# Cardy_PCB.net
KiCad netlist of a schematic drawn in EasyEDA Pro
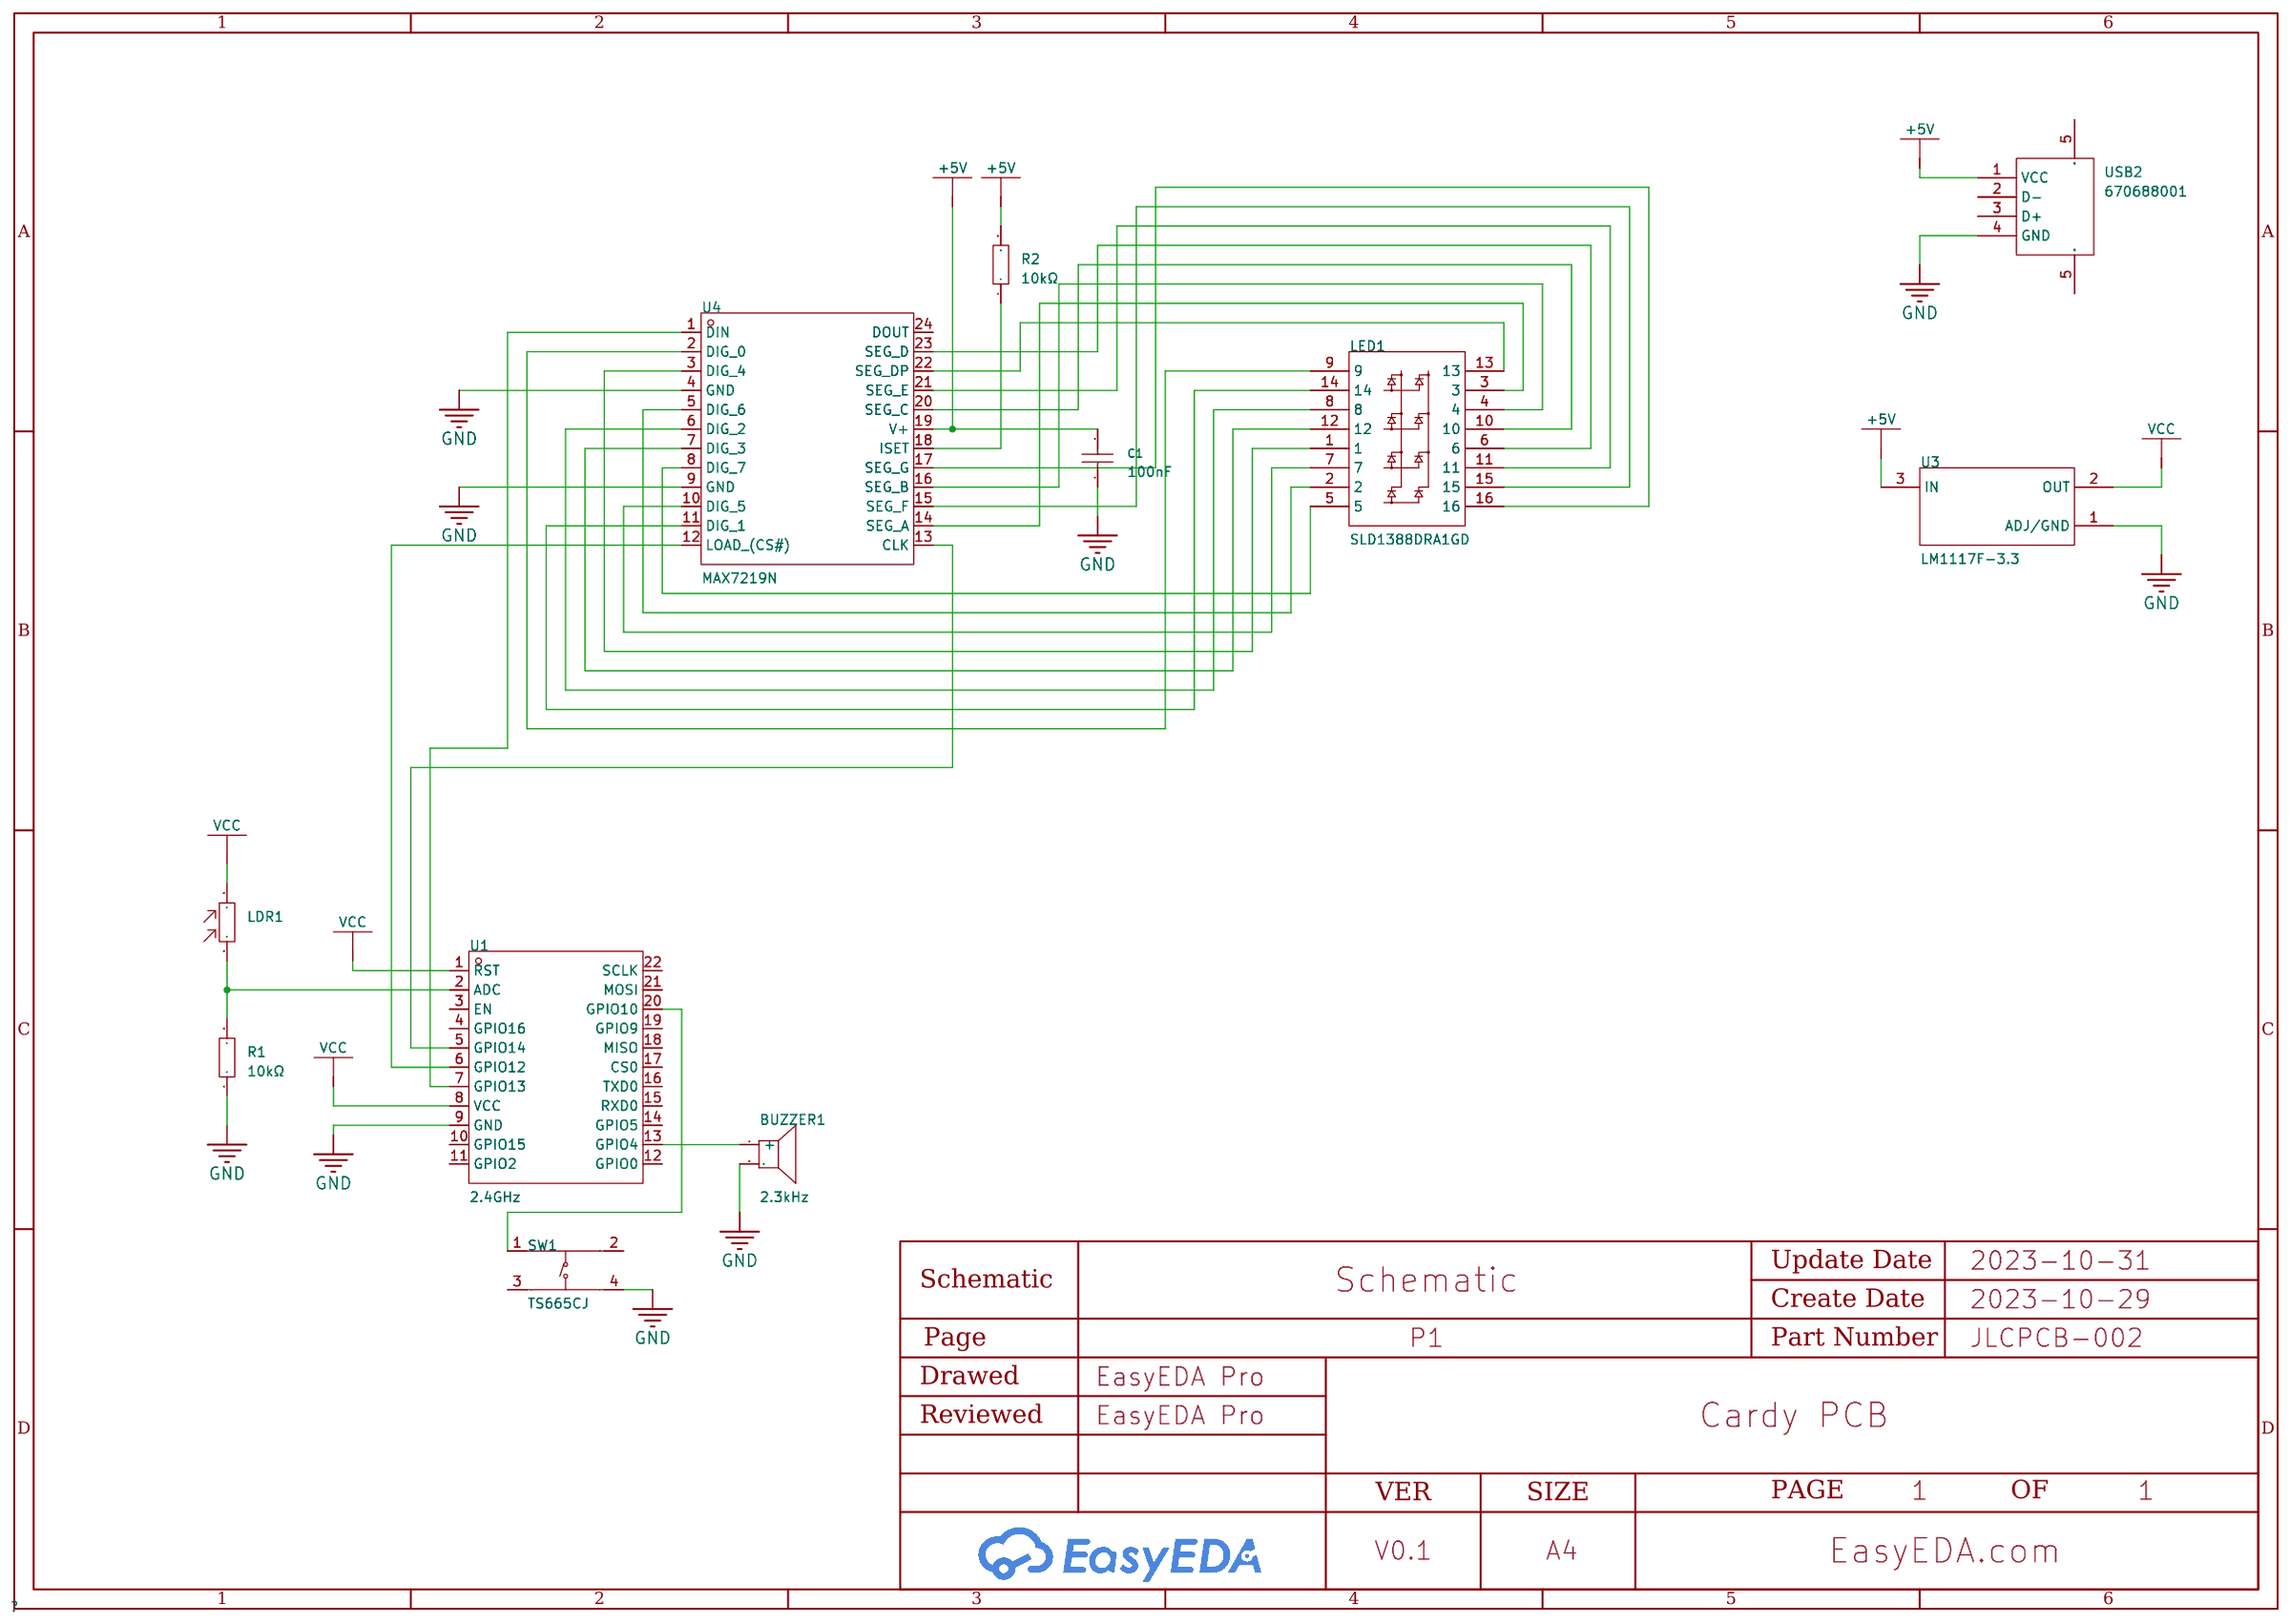
[diagram p0: schematic sheet]

(export (version "E")
  (design (tool "Eeschema 10.0.6"))
  (components
    (comp (ref "BUZZER1")
      (value "2.3kHz")
      (footprint "easyedapro:BUZ-TH_BD12.0-P7.60-D0.6-FD")
      (fields (field (name "Manufacturer Part") "TMB12A05") (field (name "Manufacturer") "华能"))
      (libsource (lib "easyedapro") (part "TMB12A05"))
    )
    (comp (ref "C1")
      (value "100nF")
      (footprint "easyedapro:CAP-TH_L5.0-W3.2-P5.00-D0.5")
      (fields (field (name "Manufacturer Part") "K104K20X7RH53H5") (field (name "Manufacturer") "VISHAY(威世)"))
      (libsource (lib "easyedapro") (part "K104K20X7RH53H5"))
    )
    (comp (ref "LDR1")
      (value "GL7520F")
      (footprint "easyedapro:RES-TH_BD9.2-P5.10-D0.5")
      (fields (field (name "Manufacturer") "JCHL(晶创和立)"))
      (libsource (lib "easyedapro") (part "GL7520F"))
    )
    (comp (ref "LED1")
      (value "SLD1388DRA1GD")
      (footprint "easyedapro:LED-TH_SLD1388DRA1GD")
      (description "Dot Matrix Number:8x8 Emitting Color:Red Polarity:共阳")
      (fields (field (name "Manufacturer") "SUNLIGHT(光华)"))
      (libsource (lib "easyedapro") (part "SLD1388DRA1GD_C2913075"))
    )
    (comp (ref "R1")
      (value "10kΩ")
      (footprint "easyedapro:R_AXIAL-0.4")
      (libsource (lib "easyedapro") (part "Res"))
    )
    (comp (ref "R2")
      (value "10kΩ")
      (footprint "easyedapro:R_AXIAL-0.4")
      (libsource (lib "easyedapro") (part "Res"))
    )
    (comp (ref "SW1")
      (value "TS665CJ")
      (footprint "easyedapro:SW-TH_4P-L6.0-W6.0-P4.50-LS6.5")
      (fields (field (name "Manufacturer") "SHOU HAN(首韩)"))
      (libsource (lib "easyedapro") (part "TS665CJ"))
    )
    (comp (ref "U1")
      (value "2.4GHz")
      (footprint "easyedapro:WIFIM-SMD_ESP-12F-ESP8266MOD")
      (fields
        (field (name "Manufacturer Part") "ESP-12F(ESP8266MOD)")
        (field (name "Manufacturer") "Ai-Thinker(安信可)")
      )
      (libsource (lib "easyedapro") (part "ESP-12F(ESP8266MOD)"))
    )
    (comp (ref "U3")
      (value "LM1117F-3.3")
      (footprint "easyedapro:SOT-89_L4.5-W2.5-P1.50-LS4.2-BR")
      (fields (field (name "Manufacturer") "HTC"))
      (libsource (lib "easyedapro") (part "LM1117F-3.3"))
    )
    (comp (ref "U4")
      (value "MAX7219N")
      (footprint "easyedapro:DIP-24_L30.5-W7.5-P2.54-LS7.6-BL")
      (fields (field (name "Manufacturer") "HGSEMI(华冠)"))
      (libsource (lib "easyedapro") (part "MAX7219N"))
    )
    (comp (ref "USB2")
      (value "670688001")
      (footprint "easyedapro:USB-B_TH_670688001")
      (description "Standard:USB 2.0")
      (fields (field (name "Manufacturer") "MOLEX"))
      (libsource (lib "easyedapro") (part "670688001"))
    )
  )
  (nets
    (net (code "1") (name "+5V") (class "Default")
      (node (ref "C1") (pin "2") (pinfunction "2_2") (pintype "input"))
      (node (ref "R2") (pin "2") (pinfunction "2_2") (pintype "input"))
      (node (ref "U3") (pin "3") (pinfunction "IN_3") (pintype "input"))
      (node (ref "U4") (pin "19") (pinfunction "V+_19") (pintype "input"))
      (node (ref "USB2") (pin "1") (pinfunction "VCC_1") (pintype "input"))
    )
    (net (code "2") (name "GND") (class "Default")
      (node (ref "BUZZER1") (pin "2") (pinfunction "2_2") (pintype "input"))
      (node (ref "C1") (pin "1") (pinfunction "1_1") (pintype "input"))
      (node (ref "R1") (pin "1") (pinfunction "1_1") (pintype "input"))
      (node (ref "SW1") (pin "4") (pinfunction "D_4") (pintype "input"))
      (node (ref "U1") (pin "9") (pinfunction "GND_9") (pintype "input"))
      (node (ref "U3") (pin "1") (pinfunction "ADJ/GND_1") (pintype "input"))
      (node (ref "U4") (pin "4") (pinfunction "GND_4") (pintype "input"))
      (node (ref "U4") (pin "9") (pinfunction "GND_9") (pintype "input"))
      (node (ref "USB2") (pin "4") (pinfunction "GND_4") (pintype "input"))
    )
    (net (code "3") (name "Net-(BUZZER1-+)") (class "Default")
      (node (ref "BUZZER1") (pin "1") (pinfunction "+_1") (pintype "input"))
      (node (ref "U1") (pin "13") (pinfunction "GPIO4_13") (pintype "input"))
    )
    (net (code "4") (name "Net-(SW1-A)") (class "Default")
      (node (ref "SW1") (pin "1") (pinfunction "A_1") (pintype "input"))
      (node (ref "U1") (pin "20") (pinfunction "GPIO10_20") (pintype "input"))
    )
    (net (code "5") (name "Net-(U1-ADC)") (class "Default")
      (node (ref "LDR1") (pin "1") (pinfunction "1_1") (pintype "input"))
      (node (ref "R1") (pin "2") (pinfunction "2_2") (pintype "input"))
      (node (ref "U1") (pin "2") (pinfunction "ADC_2") (pintype "input"))
    )
    (net (code "6") (name "Net-(U1-GPIO12)") (class "Default")
      (node (ref "U1") (pin "6") (pinfunction "GPIO12_6") (pintype "input"))
      (node (ref "U4") (pin "12") (pinfunction "LOAD_(CS#)_12") (pintype "input"))
    )
    (net (code "7") (name "Net-(U1-GPIO13)") (class "Default")
      (node (ref "U1") (pin "7") (pinfunction "GPIO13_7") (pintype "input"))
      (node (ref "U4") (pin "1") (pinfunction "DIN_1") (pintype "input"))
    )
    (net (code "8") (name "Net-(U1-GPIO14)") (class "Default")
      (node (ref "U1") (pin "5") (pinfunction "GPIO14_5") (pintype "input"))
      (node (ref "U4") (pin "13") (pinfunction "CLK_13") (pintype "input"))
    )
    (net (code "9") (name "Net-(U4-DIG_0)") (class "Default")
      (node (ref "LED1") (pin "9") (pinfunction "9_9") (pintype "input"))
      (node (ref "U4") (pin "2") (pinfunction "DIG_0_2") (pintype "input"))
    )
    (net (code "10") (name "Net-(U4-DIG_1)") (class "Default")
      (node (ref "LED1") (pin "14") (pinfunction "14_14") (pintype "input"))
      (node (ref "U4") (pin "11") (pinfunction "DIG_1_11") (pintype "input"))
    )
    (net (code "11") (name "Net-(U4-DIG_2)") (class "Default")
      (node (ref "LED1") (pin "8") (pinfunction "8_8") (pintype "input"))
      (node (ref "U4") (pin "6") (pinfunction "DIG_2_6") (pintype "input"))
    )
    (net (code "12") (name "Net-(U4-DIG_3)") (class "Default")
      (node (ref "LED1") (pin "12") (pinfunction "12_12") (pintype "input"))
      (node (ref "U4") (pin "7") (pinfunction "DIG_3_7") (pintype "input"))
    )
    (net (code "13") (name "Net-(U4-DIG_4)") (class "Default")
      (node (ref "LED1") (pin "1") (pinfunction "1_1") (pintype "input"))
      (node (ref "U4") (pin "3") (pinfunction "DIG_4_3") (pintype "input"))
    )
    (net (code "14") (name "Net-(U4-DIG_5)") (class "Default")
      (node (ref "LED1") (pin "7") (pinfunction "7_7") (pintype "input"))
      (node (ref "U4") (pin "10") (pinfunction "DIG_5_10") (pintype "input"))
    )
    (net (code "15") (name "Net-(U4-DIG_6)") (class "Default")
      (node (ref "LED1") (pin "2") (pinfunction "2_2") (pintype "input"))
      (node (ref "U4") (pin "5") (pinfunction "DIG_6_5") (pintype "input"))
    )
    (net (code "16") (name "Net-(U4-DIG_7)") (class "Default")
      (node (ref "LED1") (pin "5") (pinfunction "5_5") (pintype "input"))
      (node (ref "U4") (pin "8") (pinfunction "DIG_7_8") (pintype "input"))
    )
    (net (code "17") (name "Net-(U4-ISET)") (class "Default")
      (node (ref "R2") (pin "1") (pinfunction "1_1") (pintype "input"))
      (node (ref "U4") (pin "18") (pinfunction "ISET_18") (pintype "input"))
    )
    (net (code "18") (name "Net-(U4-SEG_A)") (class "Default")
      (node (ref "LED1") (pin "3") (pinfunction "3_3") (pintype "input"))
      (node (ref "U4") (pin "14") (pinfunction "SEG_A_14") (pintype "input"))
    )
    (net (code "19") (name "Net-(U4-SEG_B)") (class "Default")
      (node (ref "LED1") (pin "4") (pinfunction "4_4") (pintype "input"))
      (node (ref "U4") (pin "16") (pinfunction "SEG_B_16") (pintype "input"))
    )
    (net (code "20") (name "Net-(U4-SEG_C)") (class "Default")
      (node (ref "LED1") (pin "10") (pinfunction "10_10") (pintype "input"))
      (node (ref "U4") (pin "20") (pinfunction "SEG_C_20") (pintype "input"))
    )
    (net (code "21") (name "Net-(U4-SEG_D)") (class "Default")
      (node (ref "LED1") (pin "6") (pinfunction "6_6") (pintype "input"))
      (node (ref "U4") (pin "23") (pinfunction "SEG_D_23") (pintype "input"))
    )
    (net (code "22") (name "Net-(U4-SEG_DP)") (class "Default")
      (node (ref "LED1") (pin "13") (pinfunction "13_13") (pintype "input"))
      (node (ref "U4") (pin "22") (pinfunction "SEG_DP_22") (pintype "input"))
    )
    (net (code "23") (name "Net-(U4-SEG_E)") (class "Default")
      (node (ref "LED1") (pin "11") (pinfunction "11_11") (pintype "input"))
      (node (ref "U4") (pin "21") (pinfunction "SEG_E_21") (pintype "input"))
    )
    (net (code "24") (name "Net-(U4-SEG_F)") (class "Default")
      (node (ref "LED1") (pin "15") (pinfunction "15_15") (pintype "input"))
      (node (ref "U4") (pin "15") (pinfunction "SEG_F_15") (pintype "input"))
    )
    (net (code "25") (name "Net-(U4-SEG_G)") (class "Default")
      (node (ref "LED1") (pin "16") (pinfunction "16_16") (pintype "input"))
      (node (ref "U4") (pin "17") (pinfunction "SEG_G_17") (pintype "input"))
    )
    (net (code "26") (name "VCC") (class "Default")
      (node (ref "LDR1") (pin "2") (pinfunction "2_2") (pintype "input"))
      (node (ref "U1") (pin "1") (pinfunction "RST_1") (pintype "input"))
      (node (ref "U1") (pin "8") (pinfunction "VCC_8") (pintype "input"))
      (node (ref "U3") (pin "2") (pinfunction "OUT_2") (pintype "input"))
    )
    (net (code "27") (name "unconnected-(SW1-B-Pad2)") (class "Default")
      (node (ref "SW1") (pin "2") (pinfunction "B_2") (pintype "input"))
    )
    (net (code "28") (name "unconnected-(SW1-C-Pad3)") (class "Default")
      (node (ref "SW1") (pin "3") (pinfunction "C_3") (pintype "input"))
    )
    (net (code "29") (name "unconnected-(U1-CS0-Pad17)") (class "Default")
      (node (ref "U1") (pin "17") (pinfunction "CS0_17") (pintype "input"))
    )
    (net (code "30") (name "unconnected-(U1-EN-Pad3)") (class "Default")
      (node (ref "U1") (pin "3") (pinfunction "EN_3") (pintype "input"))
    )
    (net (code "31") (name "unconnected-(U1-GPIO0-Pad12)") (class "Default")
      (node (ref "U1") (pin "12") (pinfunction "GPIO0_12") (pintype "input"))
    )
    (net (code "32") (name "unconnected-(U1-GPIO2-Pad11)") (class "Default")
      (node (ref "U1") (pin "11") (pinfunction "GPIO2_11") (pintype "input"))
    )
    (net (code "33") (name "unconnected-(U1-GPIO5-Pad14)") (class "Default")
      (node (ref "U1") (pin "14") (pinfunction "GPIO5_14") (pintype "input"))
    )
    (net (code "34") (name "unconnected-(U1-GPIO9-Pad19)") (class "Default")
      (node (ref "U1") (pin "19") (pinfunction "GPIO9_19") (pintype "input"))
    )
    (net (code "35") (name "unconnected-(U1-GPIO15-Pad10)") (class "Default")
      (node (ref "U1") (pin "10") (pinfunction "GPIO15_10") (pintype "input"))
    )
    (net (code "36") (name "unconnected-(U1-GPIO16-Pad4)") (class "Default")
      (node (ref "U1") (pin "4") (pinfunction "GPIO16_4") (pintype "input"))
    )
    (net (code "37") (name "unconnected-(U1-MISO-Pad18)") (class "Default")
      (node (ref "U1") (pin "18") (pinfunction "MISO_18") (pintype "input"))
    )
    (net (code "38") (name "unconnected-(U1-MOSI-Pad21)") (class "Default")
      (node (ref "U1") (pin "21") (pinfunction "MOSI_21") (pintype "input"))
    )
    (net (code "39") (name "unconnected-(U1-RXD0-Pad15)") (class "Default")
      (node (ref "U1") (pin "15") (pinfunction "RXD0_15") (pintype "input"))
    )
    (net (code "40") (name "unconnected-(U1-SCLK-Pad22)") (class "Default")
      (node (ref "U1") (pin "22") (pinfunction "SCLK_22") (pintype "input"))
    )
    (net (code "41") (name "unconnected-(U1-TXD0-Pad16)") (class "Default")
      (node (ref "U1") (pin "16") (pinfunction "TXD0_16") (pintype "input"))
    )
    (net (code "42") (name "unconnected-(U4-DOUT-Pad24)") (class "Default")
      (node (ref "U4") (pin "24") (pinfunction "DOUT_24") (pintype "input"))
    )
    (net (code "43") (name "unconnected-(USB2-D+-Pad3)") (class "Default")
      (node (ref "USB2") (pin "3") (pinfunction "D+_3") (pintype "input"))
    )
    (net (code "44") (name "unconnected-(USB2-D--Pad2)") (class "Default")
      (node (ref "USB2") (pin "2") (pinfunction "D-_2") (pintype "input"))
    )
    (net (code "45") (name "unconnected-(USB2-SHLD-Pad5)") (class "Default")
      (node (ref "USB2") (pin "5") (pinfunction "SHLD_5") (pintype "input"))
    )
    (net (code "46") (name "unconnected-(USB2-SHLD-Pad5)_1") (class "Default")
      (node (ref "USB2") (pin "5") (pinfunction "SHLD_5") (pintype "input"))
    )
  )
)
